# Main.net
KiCad netlist of a schematic drawn in Altium Designer
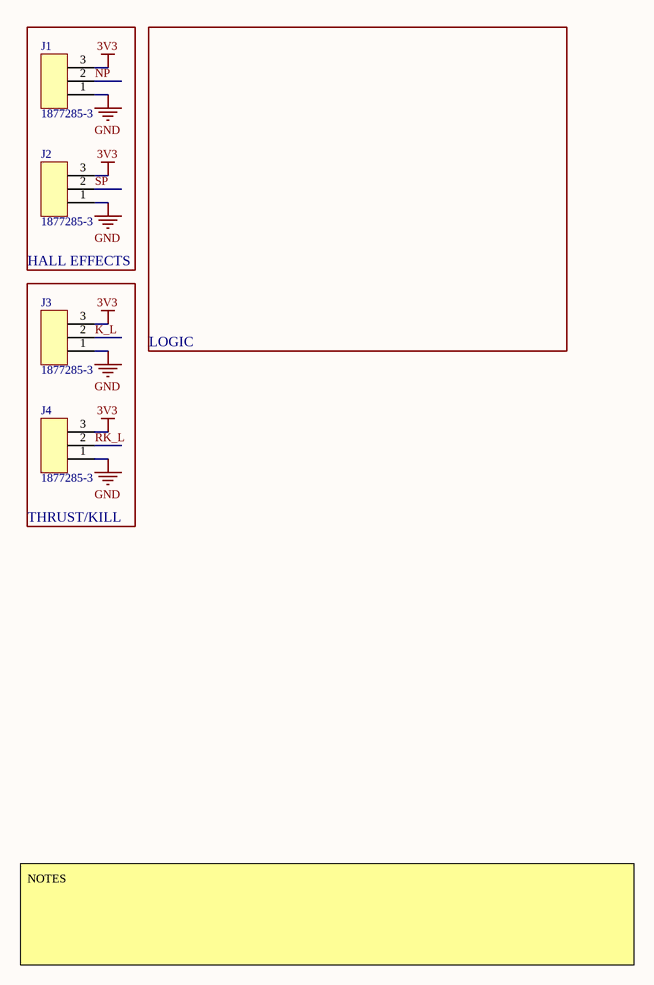
[diagram p0: Main.SchDoc]

(export (version "E")
  (design (tool "Eeschema 10.0.6"))
  (components
    (comp (ref "J1")
      (value "1877285-3")
      (footprint "1877285-3")
      (libsource (lib "AltiumAssignment") (part "1877285-3"))
    )
    (comp (ref "J2")
      (value "1877285-3")
      (footprint "1877285-3")
      (libsource (lib "AltiumAssignment") (part "1877285-3"))
    )
    (comp (ref "J3")
      (value "1877285-3")
      (footprint "1877285-3")
      (libsource (lib "AltiumAssignment") (part "1877285-3"))
    )
    (comp (ref "J4")
      (value "1877285-3")
      (footprint "1877285-3")
      (libsource (lib "AltiumAssignment") (part "1877285-3"))
    )
  )
  (nets
    (net (code "1") (name "/K_L") (class "Default")
      (node (ref "J3") (pin "2") (pinfunction "2_2") (pintype "passive"))
    )
    (net (code "2") (name "/NP") (class "Default")
      (node (ref "J1") (pin "2") (pinfunction "2_2") (pintype "passive"))
    )
    (net (code "3") (name "/RK_L") (class "Default")
      (node (ref "J4") (pin "2") (pinfunction "2_2") (pintype "passive"))
    )
    (net (code "4") (name "/SP") (class "Default")
      (node (ref "J2") (pin "2") (pinfunction "2_2") (pintype "passive"))
    )
    (net (code "5") (name "3V3") (class "Default")
      (node (ref "J1") (pin "3") (pinfunction "3_3") (pintype "passive"))
      (node (ref "J2") (pin "3") (pinfunction "3_3") (pintype "passive"))
      (node (ref "J3") (pin "3") (pinfunction "3_3") (pintype "passive"))
      (node (ref "J4") (pin "3") (pinfunction "3_3") (pintype "passive"))
    )
    (net (code "6") (name "GND") (class "Default")
      (node (ref "J1") (pin "1") (pinfunction "1_1") (pintype "passive"))
      (node (ref "J2") (pin "1") (pinfunction "1_1") (pintype "passive"))
      (node (ref "J3") (pin "1") (pinfunction "1_1") (pintype "passive"))
      (node (ref "J4") (pin "1") (pinfunction "1_1") (pintype "passive"))
    )
  )
)
